# Microcontroleur.net
KiCad netlist of a schematic drawn in Altium Designer
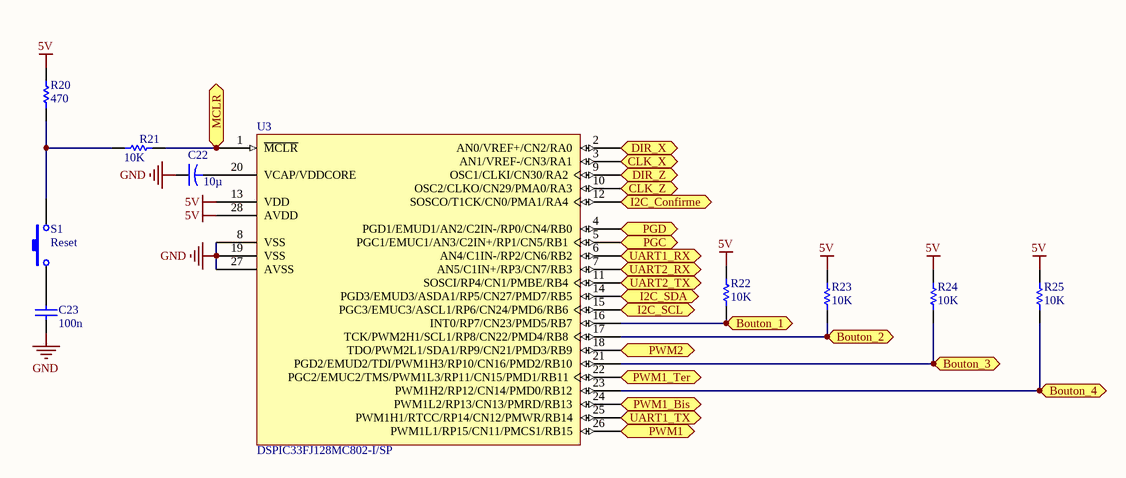
[diagram p0: Microcontroleur.SchDoc]

(export (version "E")
  (design (tool "Eeschema 10.0.6"))
  (components
    (comp (ref "C22")
      (value "10µ")
      (footprint "CAPR5-4X5")
      (description "Capacitor")
      (fields (field (name "Comment") "Cap2") (field (name "PUBLISHER") "Altium Limited"))
      (libsource (lib "Miscellaneous Devices") (part "Cap2"))
    )
    (comp (ref "C23")
      (value "100n")
      (footprint "RAD-0.3")
      (description "Capacitor")
      (fields (field (name "Comment") "Cap") (field (name "PUBLISHER") "Altium Limited"))
      (libsource (lib "Miscellaneous Devices") (part "Cap"))
    )
    (comp (ref "R20")
      (value "470")
      (footprint "AXIAL-0.3")
      (description "Resistor")
      (fields (field (name "Comment") "Res1") (field (name "PUBLISHER") "Altium Limited"))
      (libsource (lib "Miscellaneous Devices") (part "Res1"))
    )
    (comp (ref "R21")
      (value "10K")
      (footprint "AXIAL-0.3")
      (description "Resistor")
      (fields (field (name "Comment") "Res1") (field (name "PUBLISHER") "Altium Limited"))
      (libsource (lib "Miscellaneous Devices") (part "Res1"))
    )
    (comp (ref "R22")
      (value "10K")
      (footprint "AXIAL-0.3")
      (description "Resistor")
      (fields (field (name "Comment") "Res1") (field (name "PUBLISHER") "Altium Limited"))
      (libsource (lib "Miscellaneous Devices") (part "Res1"))
    )
    (comp (ref "R23")
      (value "10K")
      (footprint "AXIAL-0.3")
      (description "Resistor")
      (fields (field (name "Comment") "Res1") (field (name "PUBLISHER") "Altium Limited"))
      (libsource (lib "Miscellaneous Devices") (part "Res1"))
    )
    (comp (ref "R24")
      (value "10K")
      (footprint "AXIAL-0.3")
      (description "Resistor")
      (fields (field (name "Comment") "Res1") (field (name "PUBLISHER") "Altium Limited"))
      (libsource (lib "Miscellaneous Devices") (part "Res1"))
    )
    (comp (ref "R25")
      (value "10K")
      (footprint "AXIAL-0.3")
      (description "Resistor")
      (fields (field (name "Comment") "Res1") (field (name "PUBLISHER") "Altium Limited"))
      (libsource (lib "Miscellaneous Devices") (part "Res1"))
    )
    (comp (ref "S1")
      (value "Reset")
      (footprint "SPST-2")
      (description "Switch")
      (fields (field (name "PUBLISHER") "Altium Limited"))
      (libsource (lib "Miscellaneous Devices") (part "SW-PB"))
    )
    (comp (ref "U3")
      (value "DSPIC33FJ128MC802-I/SP")
      (footprint "SPDIP300-SP28")
      (fields (field (name "PUBLISHER") "Altium Limited"))
      (libsource (lib "Microchip DSC 16-Bit dsPIC33F") (part "DSPIC33FJ128MC802-I/SP"))
    )
  )
  (nets
    (net (code "1") (name "/Bouton_1") (class "Default")
      (node (ref "R22") (pin "2") (pinfunction "2_2") (pintype "passive"))
      (node (ref "U3") (pin "16") (pinfunction "INT0/RP7/CN23/PMD5/RB7_16") (pintype "bidirectional"))
    )
    (net (code "2") (name "/Bouton_2") (class "Default")
      (node (ref "R23") (pin "2") (pinfunction "2_2") (pintype "passive"))
      (node (ref "U3") (pin "17") (pinfunction "TCK/PWM2H1/SCL1/RP8/CN22/PMD4/RB8_17") (pintype "bidirectional"))
    )
    (net (code "3") (name "/Bouton_3") (class "Default")
      (node (ref "R24") (pin "2") (pinfunction "2_2") (pintype "passive"))
      (node (ref "U3") (pin "21") (pinfunction "PGD2/EMUD2/TDI/PWM1H3/RP10/CN16/PMD2/RB10_21") (pintype "bidirectional"))
    )
    (net (code "4") (name "/Bouton_4") (class "Default")
      (node (ref "R25") (pin "2") (pinfunction "2_2") (pintype "passive"))
      (node (ref "U3") (pin "23") (pinfunction "PWM1H2/RP12/CN14/PMD0/RB12_23") (pintype "bidirectional"))
    )
    (net (code "5") (name "/CLK_X") (class "Default")
      (node (ref "U3") (pin "3") (pinfunction "AN1/VREF-/CN3/RA1_3") (pintype "bidirectional"))
    )
    (net (code "6") (name "/CLK_Z") (class "Default")
      (node (ref "U3") (pin "10") (pinfunction "OSC2/CLKO/CN29/PMA0/RA3_10") (pintype "bidirectional"))
    )
    (net (code "7") (name "/DIR_X") (class "Default")
      (node (ref "U3") (pin "2") (pinfunction "AN0/VREF+/CN2/RA0_2") (pintype "bidirectional"))
    )
    (net (code "8") (name "/DIR_Z") (class "Default")
      (node (ref "U3") (pin "9") (pinfunction "OSC1/CLKI/CN30/RA2_9") (pintype "bidirectional"))
    )
    (net (code "9") (name "/I2C_Confirme") (class "Default")
      (node (ref "U3") (pin "12") (pinfunction "SOSCO/T1CK/CN0/PMA1/RA4_12") (pintype "bidirectional"))
    )
    (net (code "10") (name "/I2C_SCL") (class "Default")
      (node (ref "U3") (pin "15") (pinfunction "PGC3/EMUC3/ASCL1/RP6/CN24/PMD6/RB6_15") (pintype "bidirectional"))
    )
    (net (code "11") (name "/I2C_SDA") (class "Default")
      (node (ref "U3") (pin "14") (pinfunction "PGD3/EMUD3/ASDA1/RP5/CN27/PMD7/RB5_14") (pintype "bidirectional"))
    )
    (net (code "12") (name "/MCLR") (class "Default")
      (node (ref "R21") (pin "2") (pinfunction "2_2") (pintype "passive"))
      (node (ref "U3") (pin "1") (pinfunction "~{MCLR}_1") (pintype "input"))
    )
    (net (code "13") (name "/PGC") (class "Default")
      (node (ref "U3") (pin "5") (pinfunction "PGC1/EMUC1/AN3/C2IN+/RP1/CN5/RB1_5") (pintype "bidirectional"))
    )
    (net (code "14") (name "/PGD") (class "Default")
      (node (ref "U3") (pin "4") (pinfunction "PGD1/EMUD1/AN2/C2IN-/RP0/CN4/RB0_4") (pintype "bidirectional"))
    )
    (net (code "15") (name "/PWM1") (class "Default")
      (node (ref "U3") (pin "26") (pinfunction "PWM1L1/RP15/CN11/PMCS1/RB15_26") (pintype "bidirectional"))
    )
    (net (code "16") (name "/PWM1_Bis") (class "Default")
      (node (ref "U3") (pin "24") (pinfunction "PWM1L2/RP13/CN13/PMRD/RB13_24") (pintype "bidirectional"))
    )
    (net (code "17") (name "/PWM1_Ter") (class "Default")
      (node (ref "U3") (pin "22") (pinfunction "PGC2/EMUC2/TMS/PWM1L3/RP11/CN15/PMD1/RB11_22") (pintype "bidirectional"))
    )
    (net (code "18") (name "/PWM2") (class "Default")
      (node (ref "U3") (pin "18") (pinfunction "TDO/PWM2L1/SDA1/RP9/CN21/PMD3/RB9_18") (pintype "bidirectional"))
    )
    (net (code "19") (name "/UART1_RX") (class "Default")
      (node (ref "U3") (pin "6") (pinfunction "AN4/C1IN-/RP2/CN6/RB2_6") (pintype "bidirectional"))
    )
    (net (code "20") (name "/UART1_TX") (class "Default")
      (node (ref "U3") (pin "25") (pinfunction "PWM1H1/RTCC/RP14/CN12/PMWR/RB14_25") (pintype "bidirectional"))
    )
    (net (code "21") (name "/UART2_RX") (class "Default")
      (node (ref "U3") (pin "7") (pinfunction "AN5/C1IN+/RP3/CN7/RB3_7") (pintype "bidirectional"))
    )
    (net (code "22") (name "/UART2_TX") (class "Default")
      (node (ref "U3") (pin "11") (pinfunction "SOSCI/RP4/CN1/PMBE/RB4_11") (pintype "bidirectional"))
    )
    (net (code "23") (name "5V") (class "Default")
      (node (ref "R20") (pin "2") (pinfunction "2_2") (pintype "passive"))
      (node (ref "R22") (pin "1") (pinfunction "1_1") (pintype "passive"))
      (node (ref "R23") (pin "1") (pinfunction "1_1") (pintype "passive"))
      (node (ref "R24") (pin "1") (pinfunction "1_1") (pintype "passive"))
      (node (ref "R25") (pin "1") (pinfunction "1_1") (pintype "passive"))
      (node (ref "U3") (pin "13") (pinfunction "VDD_13") (pintype "power_in"))
      (node (ref "U3") (pin "28") (pinfunction "AVDD_28") (pintype "power_in"))
    )
    (net (code "24") (name "GND") (class "Default")
      (node (ref "C22") (pin "1") (pinfunction "1_1") (pintype "passive"))
      (node (ref "C23") (pin "2") (pinfunction "2_2") (pintype "passive"))
      (node (ref "U3") (pin "19") (pinfunction "VSS_19") (pintype "power_in"))
      (node (ref "U3") (pin "27") (pinfunction "AVSS_27") (pintype "power_in"))
      (node (ref "U3") (pin "8") (pinfunction "VSS_8") (pintype "power_in"))
    )
    (net (code "25") (name "Net-(C23-Pad1)") (class "Default")
      (node (ref "C23") (pin "1") (pinfunction "1_1") (pintype "passive"))
      (node (ref "S1") (pin "1") (pinfunction "1_1") (pintype "passive"))
    )
    (net (code "26") (name "Net-(R20-Pad1)") (class "Default")
      (node (ref "R20") (pin "1") (pinfunction "1_1") (pintype "passive"))
      (node (ref "R21") (pin "1") (pinfunction "1_1") (pintype "passive"))
      (node (ref "S1") (pin "2") (pinfunction "2_2") (pintype "passive"))
    )
    (net (code "27") (name "Net-(U3-VCAP{slash}VDDCORE)") (class "Default")
      (node (ref "C22") (pin "2") (pinfunction "2_2") (pintype "passive"))
      (node (ref "U3") (pin "20") (pinfunction "VCAP/VDDCORE_20") (pintype "power_in"))
    )
  )
)
